# Motors.net
KiCad netlist of a schematic drawn in Altium Designer
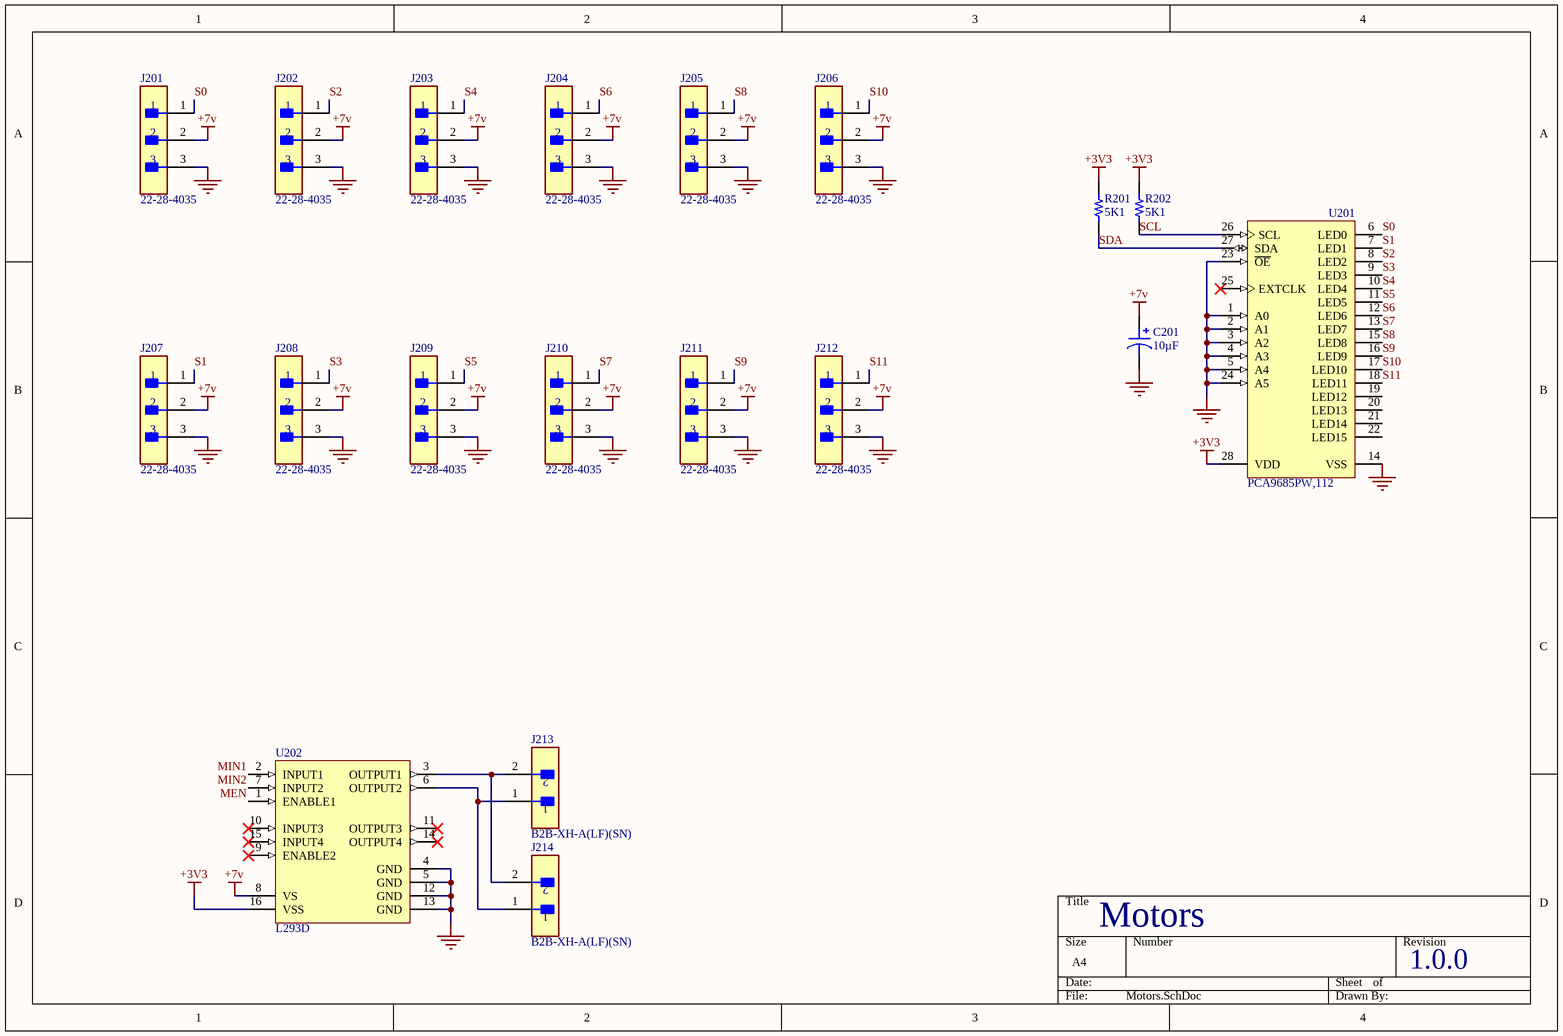
[diagram p0: Motors.SchDoc]

(export (version "E")
  (design (tool "Eeschema 10.0.6"))
  (components
    (comp (ref "C201")
      (value "10µF")
      (footprint "CAP TH ALUM ELEC D10.00mm S5.00mm H12.50mm")
      (description "CAP ALUM 10UF 20% 200V RADIAL")
      (fields (field (name "PART NUMBER") "UVR2D100MPD") (field (name "MANUFACTURER") "Nichicon"))
      (libsource (lib "Celestial Altium Library - altium_library") (part "Polarised Capacitor"))
    )
    (comp (ref "J201")
      (value "22-28-4035")
      (footprint "FP-22-28-4035-MFG")
      (libsource (lib "Altium Content Vault") (part "0d3f023dd272f625e17a2be33dea85f"))
    )
    (comp (ref "J202")
      (value "22-28-4035")
      (footprint "FP-22-28-4035-MFG")
      (libsource (lib "Altium Content Vault") (part "0d3f023dd272f625e17a2be33dea85f"))
    )
    (comp (ref "J203")
      (value "22-28-4035")
      (footprint "FP-22-28-4035-MFG")
      (libsource (lib "Altium Content Vault") (part "0d3f023dd272f625e17a2be33dea85f"))
    )
    (comp (ref "J204")
      (value "22-28-4035")
      (footprint "FP-22-28-4035-MFG")
      (libsource (lib "Altium Content Vault") (part "0d3f023dd272f625e17a2be33dea85f"))
    )
    (comp (ref "J205")
      (value "22-28-4035")
      (footprint "FP-22-28-4035-MFG")
      (libsource (lib "Altium Content Vault") (part "0d3f023dd272f625e17a2be33dea85f"))
    )
    (comp (ref "J206")
      (value "22-28-4035")
      (footprint "FP-22-28-4035-MFG")
      (libsource (lib "Altium Content Vault") (part "0d3f023dd272f625e17a2be33dea85f"))
    )
    (comp (ref "J207")
      (value "22-28-4035")
      (footprint "FP-22-28-4035-MFG")
      (libsource (lib "Altium Content Vault") (part "0d3f023dd272f625e17a2be33dea85f"))
    )
    (comp (ref "J208")
      (value "22-28-4035")
      (footprint "FP-22-28-4035-MFG")
      (libsource (lib "Altium Content Vault") (part "0d3f023dd272f625e17a2be33dea85f"))
    )
    (comp (ref "J209")
      (value "22-28-4035")
      (footprint "FP-22-28-4035-MFG")
      (libsource (lib "Altium Content Vault") (part "0d3f023dd272f625e17a2be33dea85f"))
    )
    (comp (ref "J210")
      (value "22-28-4035")
      (footprint "FP-22-28-4035-MFG")
      (libsource (lib "Altium Content Vault") (part "0d3f023dd272f625e17a2be33dea85f"))
    )
    (comp (ref "J211")
      (value "22-28-4035")
      (footprint "FP-22-28-4035-MFG")
      (libsource (lib "Altium Content Vault") (part "0d3f023dd272f625e17a2be33dea85f"))
    )
    (comp (ref "J212")
      (value "22-28-4035")
      (footprint "FP-22-28-4035-MFG")
      (libsource (lib "Altium Content Vault") (part "0d3f023dd272f625e17a2be33dea85f"))
    )
    (comp (ref "J213")
      (value "B2B-XH-A(LF)(SN)")
      (footprint "FP-B2B-XH-A_LF_SN-MFG")
      (description "CONN HEADER VERT 2POS 2.5MM")
      (libsource (lib "Altium Content Vault") (part "3bc925449376181038e59eaffc5286c"))
    )
    (comp (ref "J214")
      (value "B2B-XH-A(LF)(SN)")
      (footprint "FP-B2B-XH-A_LF_SN-MFG")
      (description "CONN HEADER VERT 2POS 2.5MM")
      (libsource (lib "Altium Content Vault") (part "3bc925449376181038e59eaffc5286c"))
    )
    (comp (ref "R201")
      (value "5K1")
      (footprint "RES 0402_1005")
      (description "RES SMD 5.1K OHM 5% 1/16W 0402")
      (fields (field (name "PART NUMBER") "AC0402JR-075K1L") (field (name "MANUFACTURER") "Yageo"))
      (libsource (lib "Celestial Altium Library - altium_library") (part "Resistor"))
    )
    (comp (ref "R202")
      (value "5K1")
      (footprint "RES 0402_1005")
      (description "RES SMD 5.1K OHM 5% 1/16W 0402")
      (fields (field (name "PART NUMBER") "AC0402JR-075K1L") (field (name "MANUFACTURER") "Yageo"))
      (libsource (lib "Celestial Altium Library - altium_library") (part "Resistor"))
    )
    (comp (ref "U201")
      (value "PCA9685PW,112")
      (footprint "SOT361-1_V")
      (fields (field (name "PARTNUMBER") "PCA9685"))
      (libsource (lib "Altium Content Vault") (part "NXP-PCA9685-SOT361-1"))
    )
    (comp (ref "U202")
      (value "L293D")
      (footprint "STM-L293D-16")
      (description "Push-Pull Four Channel Driver with Diode, 4.5 to 36 V, -40 to 150 degC, 16-Pin PDIP, RoHS, Tube")
      (fields (field (name "MANUFACTURER") "STMicroelectronics"))
      (libsource (lib "Altium Content Vault") (part "STM-L293D-16"))
    )
  )
  (nets
    (net (code "1") (name "+3V3") (class "Default")
      (node (ref "R201") (pin "2") (pinfunction "2_2") (pintype "passive"))
      (node (ref "R202") (pin "1") (pinfunction "1_1") (pintype "passive"))
      (node (ref "U201") (pin "28") (pinfunction "VDD_28") (pintype "power_in"))
      (node (ref "U202") (pin "16") (pinfunction "VSS_16") (pintype "power_in"))
    )
    (net (code "2") (name "+7v") (class "Default")
      (node (ref "C201") (pin "1") (pinfunction "1_1") (pintype "passive"))
      (node (ref "J201") (pin "2") (pinfunction "2_2") (pintype "passive"))
      (node (ref "J202") (pin "2") (pinfunction "2_2") (pintype "passive"))
      (node (ref "J203") (pin "2") (pinfunction "2_2") (pintype "passive"))
      (node (ref "J204") (pin "2") (pinfunction "2_2") (pintype "passive"))
      (node (ref "J205") (pin "2") (pinfunction "2_2") (pintype "passive"))
      (node (ref "J206") (pin "2") (pinfunction "2_2") (pintype "passive"))
      (node (ref "J207") (pin "2") (pinfunction "2_2") (pintype "passive"))
      (node (ref "J208") (pin "2") (pinfunction "2_2") (pintype "passive"))
      (node (ref "J209") (pin "2") (pinfunction "2_2") (pintype "passive"))
      (node (ref "J210") (pin "2") (pinfunction "2_2") (pintype "passive"))
      (node (ref "J211") (pin "2") (pinfunction "2_2") (pintype "passive"))
      (node (ref "J212") (pin "2") (pinfunction "2_2") (pintype "passive"))
      (node (ref "U202") (pin "8") (pinfunction "VS_8") (pintype "power_in"))
    )
    (net (code "3") (name "/MEN") (class "Default")
      (node (ref "U202") (pin "1") (pinfunction "ENABLE1_1") (pintype "input"))
    )
    (net (code "4") (name "/MIN1") (class "Default")
      (node (ref "U202") (pin "2") (pinfunction "INPUT1_2") (pintype "input"))
    )
    (net (code "5") (name "/MIN2") (class "Default")
      (node (ref "U202") (pin "7") (pinfunction "INPUT2_7") (pintype "input"))
    )
    (net (code "6") (name "/S0") (class "Default")
      (node (ref "J201") (pin "1") (pinfunction "1_1") (pintype "passive"))
      (node (ref "U201") (pin "6") (pinfunction "LED0_6") (pintype "tri_state"))
    )
    (net (code "7") (name "/S1") (class "Default")
      (node (ref "J207") (pin "1") (pinfunction "1_1") (pintype "passive"))
      (node (ref "U201") (pin "7") (pinfunction "LED1_7") (pintype "tri_state"))
    )
    (net (code "8") (name "/S2") (class "Default")
      (node (ref "J202") (pin "1") (pinfunction "1_1") (pintype "passive"))
      (node (ref "U201") (pin "8") (pinfunction "LED2_8") (pintype "tri_state"))
    )
    (net (code "9") (name "/S3") (class "Default")
      (node (ref "J208") (pin "1") (pinfunction "1_1") (pintype "passive"))
      (node (ref "U201") (pin "9") (pinfunction "LED3_9") (pintype "tri_state"))
    )
    (net (code "10") (name "/S4") (class "Default")
      (node (ref "J203") (pin "1") (pinfunction "1_1") (pintype "passive"))
      (node (ref "U201") (pin "10") (pinfunction "LED4_10") (pintype "tri_state"))
    )
    (net (code "11") (name "/S5") (class "Default")
      (node (ref "J209") (pin "1") (pinfunction "1_1") (pintype "passive"))
      (node (ref "U201") (pin "11") (pinfunction "LED5_11") (pintype "tri_state"))
    )
    (net (code "12") (name "/S6") (class "Default")
      (node (ref "J204") (pin "1") (pinfunction "1_1") (pintype "passive"))
      (node (ref "U201") (pin "12") (pinfunction "LED6_12") (pintype "tri_state"))
    )
    (net (code "13") (name "/S7") (class "Default")
      (node (ref "J210") (pin "1") (pinfunction "1_1") (pintype "passive"))
      (node (ref "U201") (pin "13") (pinfunction "LED7_13") (pintype "tri_state"))
    )
    (net (code "14") (name "/S8") (class "Default")
      (node (ref "J205") (pin "1") (pinfunction "1_1") (pintype "passive"))
      (node (ref "U201") (pin "15") (pinfunction "LED8_15") (pintype "tri_state"))
    )
    (net (code "15") (name "/S9") (class "Default")
      (node (ref "J211") (pin "1") (pinfunction "1_1") (pintype "passive"))
      (node (ref "U201") (pin "16") (pinfunction "LED9_16") (pintype "tri_state"))
    )
    (net (code "16") (name "/S10") (class "Default")
      (node (ref "J206") (pin "1") (pinfunction "1_1") (pintype "passive"))
      (node (ref "U201") (pin "17") (pinfunction "LED10_17") (pintype "tri_state"))
    )
    (net (code "17") (name "/S11") (class "Default")
      (node (ref "J212") (pin "1") (pinfunction "1_1") (pintype "passive"))
      (node (ref "U201") (pin "18") (pinfunction "LED11_18") (pintype "tri_state"))
    )
    (net (code "18") (name "/SCL") (class "Default")
      (node (ref "R202") (pin "2") (pinfunction "2_2") (pintype "passive"))
      (node (ref "U201") (pin "26") (pinfunction "SCL_26") (pintype "input"))
    )
    (net (code "19") (name "/SDA") (class "Default")
      (node (ref "R201") (pin "1") (pinfunction "1_1") (pintype "passive"))
      (node (ref "U201") (pin "27") (pinfunction "SDA_27") (pintype "bidirectional"))
    )
    (net (code "20") (name "GND") (class "Default")
      (node (ref "C201") (pin "2") (pinfunction "2_2") (pintype "passive"))
      (node (ref "J201") (pin "3") (pinfunction "3_3") (pintype "passive"))
      (node (ref "J202") (pin "3") (pinfunction "3_3") (pintype "passive"))
      (node (ref "J203") (pin "3") (pinfunction "3_3") (pintype "passive"))
      (node (ref "J204") (pin "3") (pinfunction "3_3") (pintype "passive"))
      (node (ref "J205") (pin "3") (pinfunction "3_3") (pintype "passive"))
      (node (ref "J206") (pin "3") (pinfunction "3_3") (pintype "passive"))
      (node (ref "J207") (pin "3") (pinfunction "3_3") (pintype "passive"))
      (node (ref "J208") (pin "3") (pinfunction "3_3") (pintype "passive"))
      (node (ref "J209") (pin "3") (pinfunction "3_3") (pintype "passive"))
      (node (ref "J210") (pin "3") (pinfunction "3_3") (pintype "passive"))
      (node (ref "J211") (pin "3") (pinfunction "3_3") (pintype "passive"))
      (node (ref "J212") (pin "3") (pinfunction "3_3") (pintype "passive"))
      (node (ref "U201") (pin "1") (pinfunction "A0_1") (pintype "input"))
      (node (ref "U201") (pin "14") (pinfunction "VSS_14") (pintype "power_in"))
      (node (ref "U201") (pin "2") (pinfunction "A1_2") (pintype "input"))
      (node (ref "U201") (pin "23") (pinfunction "~{OE}_23") (pintype "input"))
      (node (ref "U201") (pin "24") (pinfunction "A5_24") (pintype "input"))
      (node (ref "U201") (pin "3") (pinfunction "A2_3") (pintype "input"))
      (node (ref "U201") (pin "4") (pinfunction "A3_4") (pintype "input"))
      (node (ref "U201") (pin "5") (pinfunction "A4_5") (pintype "input"))
      (node (ref "U202") (pin "12") (pinfunction "GND_12") (pintype "power_in"))
      (node (ref "U202") (pin "13") (pinfunction "GND_13") (pintype "power_in"))
      (node (ref "U202") (pin "4") (pinfunction "GND_4") (pintype "power_in"))
      (node (ref "U202") (pin "5") (pinfunction "GND_5") (pintype "power_in"))
    )
    (net (code "21") (name "Net-(U202-OUTPUT1)") (class "Default")
      (node (ref "J213") (pin "2") (pinfunction "2_2") (pintype "passive"))
      (node (ref "J214") (pin "2") (pinfunction "2_2") (pintype "passive"))
      (node (ref "U202") (pin "3") (pinfunction "OUTPUT1_3") (pintype "output"))
    )
    (net (code "22") (name "Net-(U202-OUTPUT2)") (class "Default")
      (node (ref "J213") (pin "1") (pinfunction "1_1") (pintype "passive"))
      (node (ref "J214") (pin "1") (pinfunction "1_1") (pintype "passive"))
      (node (ref "U202") (pin "6") (pinfunction "OUTPUT2_6") (pintype "output"))
    )
    (net (code "23") (name "unconnected-(U201-EXTCLK-Pad25)") (class "Default")
      (node (ref "U201") (pin "25") (pinfunction "EXTCLK_25") (pintype "input+no_connect"))
    )
    (net (code "24") (name "unconnected-(U201-LED12-Pad19)") (class "Default")
      (node (ref "U201") (pin "19") (pinfunction "LED12_19") (pintype "tri_state"))
    )
    (net (code "25") (name "unconnected-(U201-LED13-Pad20)") (class "Default")
      (node (ref "U201") (pin "20") (pinfunction "LED13_20") (pintype "tri_state"))
    )
    (net (code "26") (name "unconnected-(U201-LED14-Pad21)") (class "Default")
      (node (ref "U201") (pin "21") (pinfunction "LED14_21") (pintype "tri_state"))
    )
    (net (code "27") (name "unconnected-(U201-LED15-Pad22)") (class "Default")
      (node (ref "U201") (pin "22") (pinfunction "LED15_22") (pintype "tri_state"))
    )
    (net (code "28") (name "unconnected-(U202-ENABLE2-Pad9)") (class "Default")
      (node (ref "U202") (pin "9") (pinfunction "ENABLE2_9") (pintype "input+no_connect"))
    )
    (net (code "29") (name "unconnected-(U202-INPUT3-Pad10)") (class "Default")
      (node (ref "U202") (pin "10") (pinfunction "INPUT3_10") (pintype "input+no_connect"))
    )
    (net (code "30") (name "unconnected-(U202-INPUT4-Pad15)") (class "Default")
      (node (ref "U202") (pin "15") (pinfunction "INPUT4_15") (pintype "input+no_connect"))
    )
    (net (code "31") (name "unconnected-(U202-OUTPUT3-Pad11)") (class "Default")
      (node (ref "U202") (pin "11") (pinfunction "OUTPUT3_11") (pintype "output+no_connect"))
    )
    (net (code "32") (name "unconnected-(U202-OUTPUT4-Pad14)") (class "Default")
      (node (ref "U202") (pin "14") (pinfunction "OUTPUT4_14") (pintype "output+no_connect"))
    )
  )
)
